# yBrainA1-11March2015.net
KiCad netlist of a schematic drawn in EAGLE
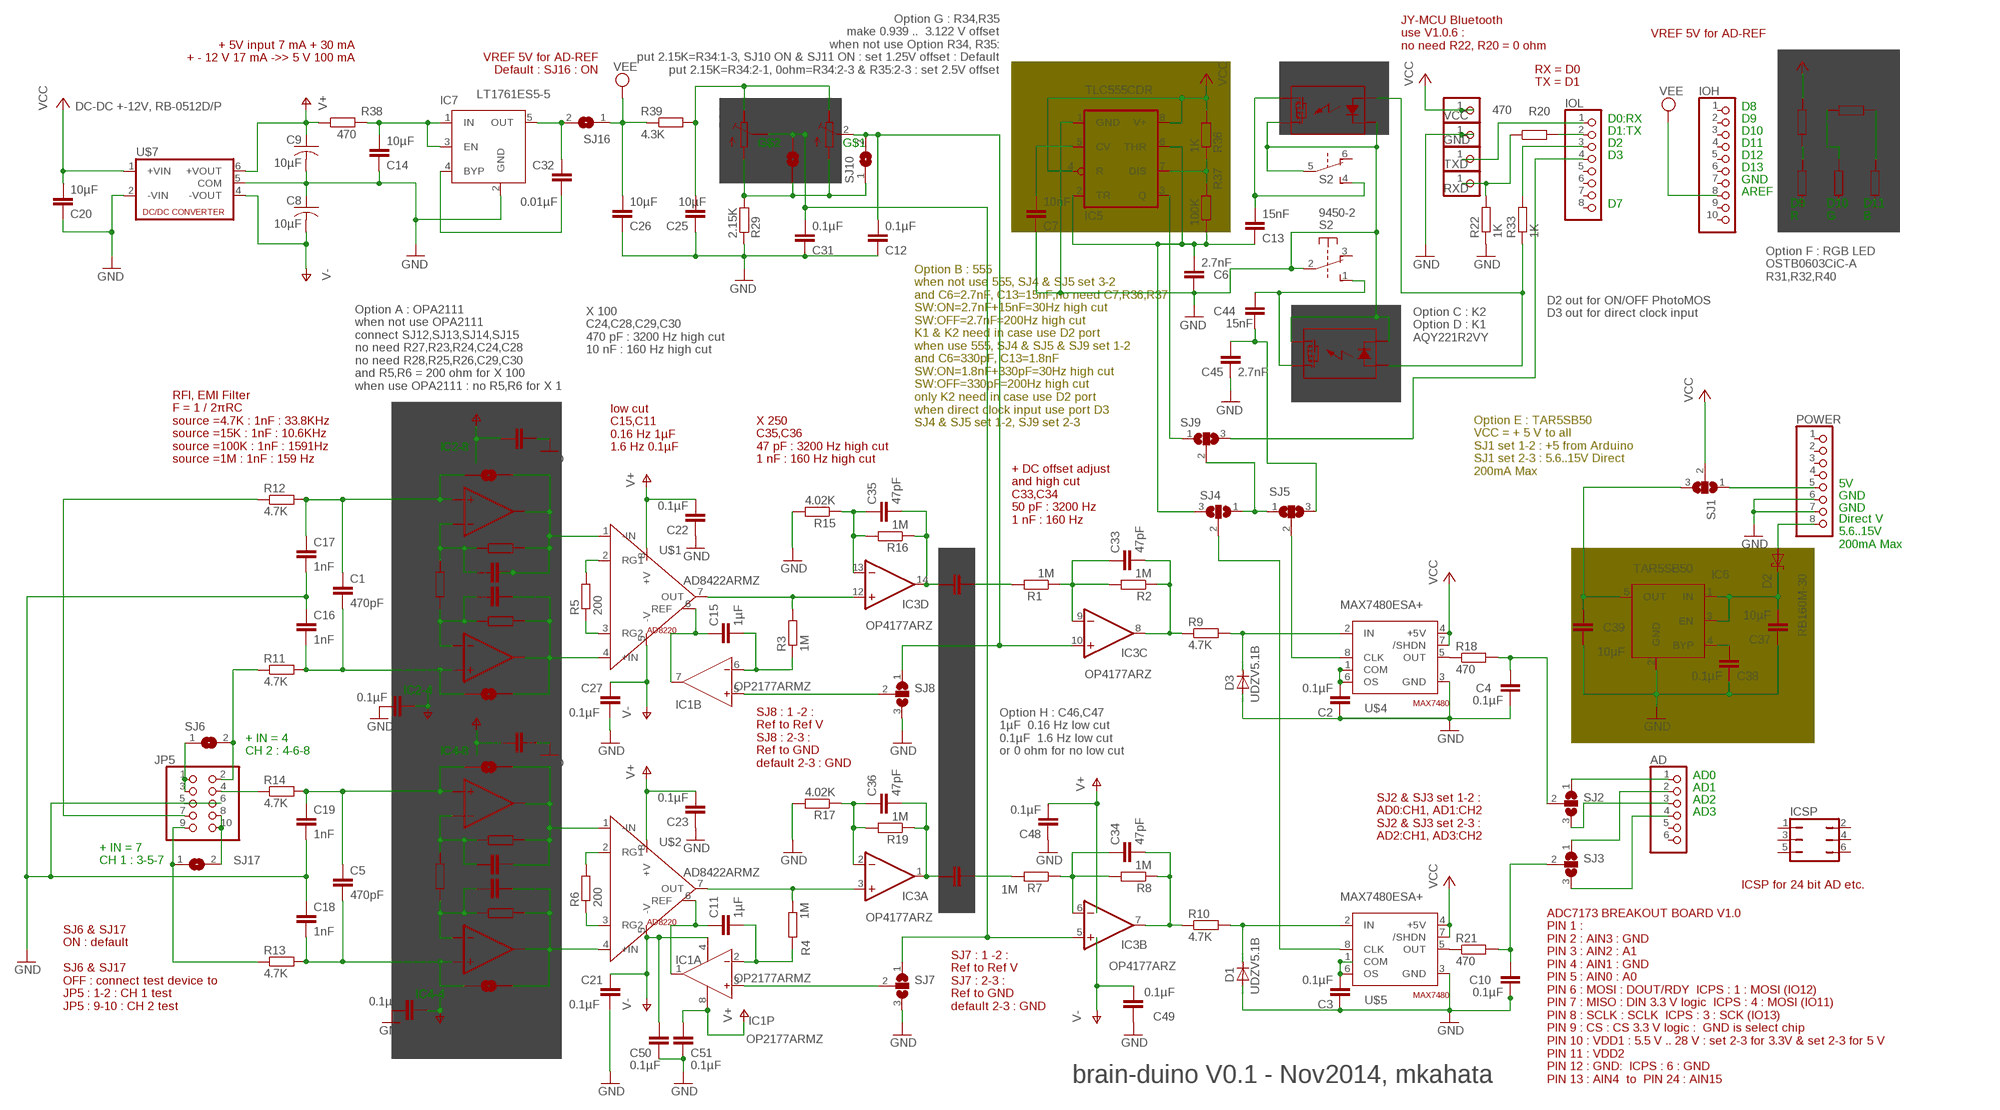
[diagram p0: schematic, sheet 1]

(export (version "E")
  (design (tool "Eeschema 10.0.6"))
  (components
    (comp (ref "AD")
      (value "PINHD-1X6")
      (footprint "eagle-import:1X06")
      (libsource (lib "eagle-import") (part "PINHD-1X6"))
    )
    (comp (ref "C1")
      (value "470pF")
      (footprint "eagle-import:C0805")
      (libsource (lib "eagle-import") (part "C-EUC0805"))
    )
    (comp (ref "C2")
      (value "0.1µF")
      (footprint "eagle-import:C0805")
      (libsource (lib "eagle-import") (part "C-EUC0805"))
    )
    (comp (ref "C3")
      (value "0.1µF")
      (footprint "eagle-import:C0805")
      (libsource (lib "eagle-import") (part "C-EUC0805"))
    )
    (comp (ref "C4")
      (value "0.1µF")
      (footprint "eagle-import:C0805")
      (libsource (lib "eagle-import") (part "C-EUC0805"))
    )
    (comp (ref "C5")
      (value "470pF")
      (footprint "eagle-import:C0805")
      (libsource (lib "eagle-import") (part "C-EUC0805"))
    )
    (comp (ref "C6")
      (value "2.7nF")
      (footprint "eagle-import:C0805")
      (libsource (lib "eagle-import") (part "C-EUC0805"))
    )
    (comp (ref "C7")
      (value "10nF")
      (footprint "eagle-import:C0805")
      (libsource (lib "eagle-import") (part "C-EUC0805"))
    )
    (comp (ref "C8")
      (value "10µF")
      (footprint "eagle-import:C0805")
      (libsource (lib "eagle-import") (part "C-USC0805"))
    )
    (comp (ref "C9")
      (value "10µF")
      (footprint "eagle-import:C0805")
      (libsource (lib "eagle-import") (part "C-USC0805"))
    )
    (comp (ref "C10")
      (value "0.1µF")
      (footprint "eagle-import:C0805")
      (libsource (lib "eagle-import") (part "C-EUC0805"))
    )
    (comp (ref "C11")
      (value "1µF")
      (footprint "eagle-import:C0805")
      (libsource (lib "eagle-import") (part "C-EUC0805"))
    )
    (comp (ref "C12")
      (value "0.1µF")
      (footprint "eagle-import:C0805")
      (libsource (lib "eagle-import") (part "C-EUC0805"))
    )
    (comp (ref "C13")
      (value "15nF")
      (footprint "eagle-import:C0805")
      (libsource (lib "eagle-import") (part "C-EUC0805"))
    )
    (comp (ref "C14")
      (value "10µF")
      (footprint "eagle-import:C0805")
      (libsource (lib "eagle-import") (part "C-EUC0805"))
    )
    (comp (ref "C15")
      (value "1µF")
      (footprint "eagle-import:C0805")
      (libsource (lib "eagle-import") (part "C-EUC0805"))
    )
    (comp (ref "C16")
      (value "1nF")
      (footprint "eagle-import:C0805")
      (libsource (lib "eagle-import") (part "C-EUC0805"))
    )
    (comp (ref "C17")
      (value "1nF")
      (footprint "eagle-import:C0805")
      (libsource (lib "eagle-import") (part "C-EUC0805"))
    )
    (comp (ref "C18")
      (value "1nF")
      (footprint "eagle-import:C0805")
      (libsource (lib "eagle-import") (part "C-EUC0805"))
    )
    (comp (ref "C19")
      (value "1nF")
      (footprint "eagle-import:C0805")
      (libsource (lib "eagle-import") (part "C-EUC0805"))
    )
    (comp (ref "C20")
      (value "10µF")
      (footprint "eagle-import:C0805")
      (libsource (lib "eagle-import") (part "C-EUC0805"))
    )
    (comp (ref "C21")
      (value "0.1µF")
      (footprint "eagle-import:C0805")
      (libsource (lib "eagle-import") (part "C-EUC0805"))
    )
    (comp (ref "C22")
      (value "0.1µF")
      (footprint "eagle-import:C0805")
      (libsource (lib "eagle-import") (part "C-EUC0805"))
    )
    (comp (ref "C23")
      (value "0.1µF")
      (footprint "eagle-import:C0805")
      (libsource (lib "eagle-import") (part "C-EUC0805"))
    )
    (comp (ref "C24")
      (value "470pF")
      (footprint "eagle-import:C0805")
      (libsource (lib "eagle-import") (part "C-EUC0805"))
    )
    (comp (ref "C25")
      (value "10µF")
      (footprint "eagle-import:C0805")
      (libsource (lib "eagle-import") (part "C-EUC0805"))
    )
    (comp (ref "C26")
      (value "10µF")
      (footprint "eagle-import:C0805")
      (libsource (lib "eagle-import") (part "C-EUC0805"))
    )
    (comp (ref "C27")
      (value "0.1µF")
      (footprint "eagle-import:C0805")
      (libsource (lib "eagle-import") (part "C-EUC0805"))
    )
    (comp (ref "C28")
      (value "470pF")
      (footprint "eagle-import:C0805")
      (libsource (lib "eagle-import") (part "C-EUC0805"))
    )
    (comp (ref "C29")
      (value "470pF")
      (footprint "eagle-import:C0805")
      (libsource (lib "eagle-import") (part "C-EUC0805"))
    )
    (comp (ref "C30")
      (value "470pF")
      (footprint "eagle-import:C0805")
      (libsource (lib "eagle-import") (part "C-EUC0805"))
    )
    (comp (ref "C31")
      (value "0.1µF")
      (footprint "eagle-import:C0805")
      (libsource (lib "eagle-import") (part "C-EUC0805"))
    )
    (comp (ref "C32")
      (value "0.01µF")
      (footprint "eagle-import:C0805")
      (libsource (lib "eagle-import") (part "C-EUC0805"))
    )
    (comp (ref "C33")
      (value "47pF")
      (footprint "eagle-import:C0805")
      (libsource (lib "eagle-import") (part "C-EUC0805"))
    )
    (comp (ref "C34")
      (value "47pF")
      (footprint "eagle-import:C0805")
      (libsource (lib "eagle-import") (part "C-EUC0805"))
    )
    (comp (ref "C35")
      (value "47pF")
      (footprint "eagle-import:C0805")
      (libsource (lib "eagle-import") (part "C-EUC0805"))
    )
    (comp (ref "C36")
      (value "47pF")
      (footprint "eagle-import:C0805")
      (libsource (lib "eagle-import") (part "C-EUC0805"))
    )
    (comp (ref "C37")
      (value "10µF")
      (footprint "eagle-import:C0805")
      (libsource (lib "eagle-import") (part "C-EUC0805"))
    )
    (comp (ref "C38")
      (value "0.1µF")
      (footprint "eagle-import:C0805")
      (libsource (lib "eagle-import") (part "C-EUC0805"))
    )
    (comp (ref "C39")
      (value "10µF")
      (footprint "eagle-import:C0805")
      (libsource (lib "eagle-import") (part "C-EUC0805"))
    )
    (comp (ref "C40")
      (value "0.1µF")
      (footprint "eagle-import:C0805")
      (libsource (lib "eagle-import") (part "C-EUC0805"))
    )
    (comp (ref "C41")
      (value "0.1µF")
      (footprint "eagle-import:C0805")
      (libsource (lib "eagle-import") (part "C-EUC0805"))
    )
    (comp (ref "C42")
      (value "0.1µF")
      (footprint "eagle-import:C0805")
      (libsource (lib "eagle-import") (part "C-EUC0805"))
    )
    (comp (ref "C43")
      (value "0.1µF")
      (footprint "eagle-import:C0805")
      (libsource (lib "eagle-import") (part "C-EUC0805"))
    )
    (comp (ref "C44")
      (value "15nF")
      (footprint "eagle-import:C0805")
      (libsource (lib "eagle-import") (part "C-EUC0805"))
    )
    (comp (ref "C45")
      (value "2.7nF")
      (footprint "eagle-import:C0805")
      (libsource (lib "eagle-import") (part "C-EUC0805"))
    )
    (comp (ref "C46")
      (value "1µF")
      (footprint "eagle-import:C0805")
      (libsource (lib "eagle-import") (part "C-EUC0805"))
    )
    (comp (ref "C47")
      (value "1µF")
      (footprint "eagle-import:C0805")
      (libsource (lib "eagle-import") (part "C-EUC0805"))
    )
    (comp (ref "C48")
      (value "0.1µF")
      (footprint "eagle-import:C0805")
      (libsource (lib "eagle-import") (part "C-EUC0805"))
    )
    (comp (ref "C49")
      (value "0.1µF")
      (footprint "eagle-import:C0805")
      (libsource (lib "eagle-import") (part "C-EUC0805"))
    )
    (comp (ref "C50")
      (value "0.1µF")
      (footprint "eagle-import:C0805")
      (libsource (lib "eagle-import") (part "C-EUC0805"))
    )
    (comp (ref "C51")
      (value "0.1µF")
      (footprint "eagle-import:C0805")
      (libsource (lib "eagle-import") (part "C-EUC0805"))
    )
    (comp (ref "D1")
      (value "UDZV5.1B")
      (footprint "eagle-import:SOD110-R")
      (libsource (lib "eagle-import") (part "DIODE-SOD110-R"))
    )
    (comp (ref "D2")
      (value "RB160M-30")
      (footprint "eagle-import:POWERDI323")
      (libsource (lib "eagle-import") (part "PD3S160"))
    )
    (comp (ref "D3")
      (value "UDZV5.1B")
      (footprint "eagle-import:SOD110-R")
      (libsource (lib "eagle-import") (part "DIODE-SOD110-R"))
    )
    (comp (ref "GND")
      (value "PINHD-1X1")
      (footprint "eagle-import:1X01")
      (libsource (lib "eagle-import") (part "PINHD-1X1"))
    )
    (comp (ref "IC1")
      (value "OP2177ARMZ")
      (footprint "eagle-import:MSOP08")
      (fields (field (name "MPN") "AD8656ARMZ"))
      (libsource (lib "eagle-import") (part "AD8656RM"))
    )
    (comp (ref "IC2")
      (value "OPA2111KP")
      (footprint "eagle-import:DIL08")
      (libsource (lib "eagle-import") (part "OPA2111P"))
    )
    (comp (ref "IC3")
      (value "OP4177ARZ")
      (footprint "eagle-import:SO14")
      (libsource (lib "eagle-import") (part "TL064D"))
    )
    (comp (ref "IC4")
      (value "OPA2111KP")
      (footprint "eagle-import:DIL08")
      (libsource (lib "eagle-import") (part "OPA2111P"))
    )
    (comp (ref "IC5")
      (value "TLC555CDR")
      (footprint "eagle-import:SO08")
      (libsource (lib "eagle-import") (part "555DLM"))
    )
    (comp (ref "IC6")
      (value "TAR5SB50")
      (footprint "eagle-import:SOT23-5")
      (libsource (lib "eagle-import") (part "MIC5219XX"))
    )
    (comp (ref "IC7")
      (value "LT1761ES5-5")
      (footprint "eagle-import:SOT23-5")
      (libsource (lib "eagle-import") (part "MIC5219XX"))
    )
    (comp (ref "ICSP")
      (value "JP3Q")
      (footprint "eagle-import:JP3Q")
      (libsource (lib "eagle-import") (part "JP3Q"))
    )
    (comp (ref "IOH")
      (value "PINHD-1X10")
      (footprint "eagle-import:1X10")
      (libsource (lib "eagle-import") (part "PINHD-1X10"))
    )
    (comp (ref "IOL")
      (value "PINHD-1X8")
      (footprint "eagle-import:1X08")
      (libsource (lib "eagle-import") (part "PINHD-1X8"))
    )
    (comp (ref "JP5")
      (value "PINHD-2X5/90")
      (footprint "eagle-import:2X05_90")
      (libsource (lib "eagle-import") (part "PINHD-2X5/90"))
    )
    (comp (ref "K1")
      (value "AQY221R2VY")
      (footprint "eagle-import:SSOP4")
      (fields (field (name "MF") "AROMAT/ MATSUSHITA") (field (name "MPN") "AQY221R2V"))
      (libsource (lib "eagle-import") (part "AQY2212VR"))
    )
    (comp (ref "K2")
      (value "AQY221R2VY")
      (footprint "eagle-import:SSOP4")
      (fields (field (name "MF") "AROMAT/ MATSUSHITA") (field (name "MPN") "AQY221R2V"))
      (libsource (lib "eagle-import") (part "AQY2212VR"))
    )
    (comp (ref "POWER")
      (value "PINHD-1X8")
      (footprint "eagle-import:1X08")
      (libsource (lib "eagle-import") (part "PINHD-1X8"))
    )
    (comp (ref "R1")
      (value "1M")
      (footprint "eagle-import:R0805")
      (libsource (lib "eagle-import") (part "R-EU_R0805"))
    )
    (comp (ref "R2")
      (value "1M")
      (footprint "eagle-import:R0805")
      (libsource (lib "eagle-import") (part "R-EU_R0805"))
    )
    (comp (ref "R3")
      (value "1M")
      (footprint "eagle-import:R0805")
      (libsource (lib "eagle-import") (part "R-EU_R0805"))
    )
    (comp (ref "R4")
      (value "1M")
      (footprint "eagle-import:R0805")
      (libsource (lib "eagle-import") (part "R-EU_R0805"))
    )
    (comp (ref "R5")
      (value "200")
      (footprint "eagle-import:R0805")
      (libsource (lib "eagle-import") (part "R-EU_R0805"))
    )
    (comp (ref "R6")
      (value "200")
      (footprint "eagle-import:R0805")
      (libsource (lib "eagle-import") (part "R-EU_R0805"))
    )
    (comp (ref "R7")
      (value "1M")
      (footprint "eagle-import:R0805")
      (libsource (lib "eagle-import") (part "R-EU_R0805"))
    )
    (comp (ref "R8")
      (value "1M")
      (footprint "eagle-import:R0805")
      (libsource (lib "eagle-import") (part "R-EU_R0805"))
    )
    (comp (ref "R9")
      (value "4.7K")
      (footprint "eagle-import:R0805")
      (libsource (lib "eagle-import") (part "R-EU_R0805"))
    )
    (comp (ref "R10")
      (value "4.7K")
      (footprint "eagle-import:R0805")
      (libsource (lib "eagle-import") (part "R-EU_R0805"))
    )
    (comp (ref "R11")
      (value "4.7K")
      (footprint "eagle-import:R0805")
      (libsource (lib "eagle-import") (part "R-EU_R0805"))
    )
    (comp (ref "R12")
      (value "4.7K")
      (footprint "eagle-import:R0805")
      (libsource (lib "eagle-import") (part "R-EU_R0805"))
    )
    (comp (ref "R13")
      (value "4.7K")
      (footprint "eagle-import:R0805")
      (libsource (lib "eagle-import") (part "R-EU_R0805"))
    )
    (comp (ref "R14")
      (value "4.7K")
      (footprint "eagle-import:R0805")
      (libsource (lib "eagle-import") (part "R-EU_R0805"))
    )
    (comp (ref "R15")
      (value "4.02K")
      (footprint "eagle-import:R0805")
      (libsource (lib "eagle-import") (part "R-EU_R0805"))
    )
    (comp (ref "R16")
      (value "1M")
      (footprint "eagle-import:R0805")
      (libsource (lib "eagle-import") (part "R-EU_R0805"))
    )
    (comp (ref "R17")
      (value "4.02K")
      (footprint "eagle-import:R0805")
      (libsource (lib "eagle-import") (part "R-EU_R0805"))
    )
    (comp (ref "R18")
      (value "470")
      (footprint "eagle-import:R0805")
      (libsource (lib "eagle-import") (part "R-EU_R0805"))
    )
    (comp (ref "R19")
      (value "1M")
      (footprint "eagle-import:R0805")
      (libsource (lib "eagle-import") (part "R-EU_R0805"))
    )
    (comp (ref "R20")
      (value "470")
      (footprint "eagle-import:R0805")
      (libsource (lib "eagle-import") (part "R-EU_R0805"))
    )
    (comp (ref "R21")
      (value "470")
      (footprint "eagle-import:R0805")
      (libsource (lib "eagle-import") (part "R-EU_R0805"))
    )
    (comp (ref "R22")
      (value "1K")
      (footprint "eagle-import:R0805")
      (libsource (lib "eagle-import") (part "R-EU_R0805"))
    )
    (comp (ref "R23")
      (value "100K")
      (footprint "eagle-import:R0805")
      (libsource (lib "eagle-import") (part "R-EU_R0805"))
    )
    (comp (ref "R24")
      (value "100K")
      (footprint "eagle-import:R0805")
      (libsource (lib "eagle-import") (part "R-EU_R0805"))
    )
    (comp (ref "R25")
      (value "100K")
      (footprint "eagle-import:R0805")
      (libsource (lib "eagle-import") (part "R-EU_R0805"))
    )
    (comp (ref "R26")
      (value "100K")
      (footprint "eagle-import:R0805")
      (libsource (lib "eagle-import") (part "R-EU_R0805"))
    )
    (comp (ref "R27")
      (value "2K")
      (footprint "eagle-import:R0805")
      (libsource (lib "eagle-import") (part "R-EU_R0805"))
    )
    (comp (ref "R28")
      (value "2K")
      (footprint "eagle-import:R0805")
      (libsource (lib "eagle-import") (part "R-EU_R0805"))
    )
    (comp (ref "R29")
      (value "2.15K")
      (footprint "eagle-import:R0805")
      (libsource (lib "eagle-import") (part "R-EU_R0805"))
    )
    (comp (ref "R30")
      (value "LED")
      (footprint "eagle-import:R0402")
      (libsource (lib "eagle-import") (part "R-EU_R0402"))
    )
    (comp (ref "R31")
      (value "1K")
      (footprint "eagle-import:R0402")
      (libsource (lib "eagle-import") (part "R-EU_R0402"))
    )
    (comp (ref "R32")
      (value "1K")
      (footprint "eagle-import:R0402")
      (libsource (lib "eagle-import") (part "R-EU_R0402"))
    )
    (comp (ref "R33")
      (value "1K")
      (footprint "eagle-import:R0805")
      (libsource (lib "eagle-import") (part "R-EU_R0805"))
    )
    (comp (ref "R34")
      (value "10K")
      (footprint "eagle-import:RTRIM5X")
      (libsource (lib "eagle-import") (part "R-TRIMM5X"))
    )
    (comp (ref "R35")
      (value "10K")
      (footprint "eagle-import:RTRIM5X")
      (libsource (lib "eagle-import") (part "R-TRIMM5X"))
    )
    (comp (ref "R36")
      (value "1K")
      (footprint "eagle-import:R0805")
      (libsource (lib "eagle-import") (part "R-EU_R0805"))
    )
    (comp (ref "R37")
      (value "100K")
      (footprint "eagle-import:R0805")
      (libsource (lib "eagle-import") (part "R-EU_R0805"))
    )
    (comp (ref "R38")
      (value "470")
      (footprint "eagle-import:R0805")
      (libsource (lib "eagle-import") (part "R-EU_R0805"))
    )
    (comp (ref "R39")
      (value "4.3K")
      (footprint "eagle-import:R0805")
      (libsource (lib "eagle-import") (part "R-EU_R0805"))
    )
    (comp (ref "R40")
      (value "1K")
      (footprint "eagle-import:R0402")
      (libsource (lib "eagle-import") (part "R-EU_R0402"))
    )
    (comp (ref "R41")
      (value "LED")
      (footprint "eagle-import:R0402")
      (libsource (lib "eagle-import") (part "R-EU_R0402"))
    )
    (comp (ref "RXD")
      (value "PINHD-1X1")
      (footprint "eagle-import:1X01")
      (libsource (lib "eagle-import") (part "PINHD-1X1"))
    )
    (comp (ref "S2")
      (value "9450-2")
      (footprint "eagle-import:9450-2")
      (libsource (lib "eagle-import") (part "9450-2"))
    )
    (comp (ref "SJ1")
      (value "SJ2W")
      (footprint "eagle-import:SJ_2")
      (libsource (lib "eagle-import") (part "SJ2W"))
    )
    (comp (ref "SJ2")
      (value "SJ2W")
      (footprint "eagle-import:SJ_2")
      (libsource (lib "eagle-import") (part "SJ2W"))
    )
    (comp (ref "SJ3")
      (value "SJ2W")
      (footprint "eagle-import:SJ_2")
      (libsource (lib "eagle-import") (part "SJ2W"))
    )
    (comp (ref "SJ4")
      (value "SJ2W")
      (footprint "eagle-import:SJ_2")
      (libsource (lib "eagle-import") (part "SJ2W"))
    )
    (comp (ref "SJ5")
      (value "SJ2W")
      (footprint "eagle-import:SJ_2")
      (libsource (lib "eagle-import") (part "SJ2W"))
    )
    (comp (ref "SJ6") (value "SJ") (footprint "eagle-import:SJ") (libsource (lib "eagle-import") (part "SJ")))
    (comp (ref "SJ7")
      (value "SJ2W")
      (footprint "eagle-import:SJ_2")
      (libsource (lib "eagle-import") (part "SJ2W"))
    )
    (comp (ref "SJ8")
      (value "SJ2W")
      (footprint "eagle-import:SJ_2")
      (libsource (lib "eagle-import") (part "SJ2W"))
    )
    (comp (ref "SJ9")
      (value "SJ2W")
      (footprint "eagle-import:SJ_2")
      (libsource (lib "eagle-import") (part "SJ2W"))
    )
    (comp (ref "SJ10")
      (value "SJ")
      (footprint "eagle-import:SJ")
      (libsource (lib "eagle-import") (part "SJ"))
    )
    (comp (ref "SJ11")
      (value "SJ")
      (footprint "eagle-import:SJ")
      (libsource (lib "eagle-import") (part "SJ"))
    )
    (comp (ref "SJ12")
      (value "SJ")
      (footprint "eagle-import:SJ")
      (libsource (lib "eagle-import") (part "SJ"))
    )
    (comp (ref "SJ13")
      (value "SJ")
      (footprint "eagle-import:SJ")
      (libsource (lib "eagle-import") (part "SJ"))
    )
    (comp (ref "SJ14")
      (value "SJ")
      (footprint "eagle-import:SJ")
      (libsource (lib "eagle-import") (part "SJ"))
    )
    (comp (ref "SJ15")
      (value "SJ")
      (footprint "eagle-import:SJ")
      (libsource (lib "eagle-import") (part "SJ"))
    )
    (comp (ref "SJ16")
      (value "SJ")
      (footprint "eagle-import:SJ")
      (libsource (lib "eagle-import") (part "SJ"))
    )
    (comp (ref "SJ17")
      (value "SJ")
      (footprint "eagle-import:SJ")
      (libsource (lib "eagle-import") (part "SJ"))
    )
    (comp (ref "TXD")
      (value "PINHD-1X1")
      (footprint "eagle-import:1X01")
      (libsource (lib "eagle-import") (part "PINHD-1X1"))
    )
    (comp (ref "U$1")
      (value "AD8422ARMZ")
      (footprint "eagle-import:AD8220")
      (libsource (lib "eagle-import") (part "AD8220"))
    )
    (comp (ref "U$2")
      (value "AD8422ARMZ")
      (footprint "eagle-import:AD8220")
      (libsource (lib "eagle-import") (part "AD8220"))
    )
    (comp (ref "U$4")
      (value "MAX7480ESA+")
      (footprint "eagle-import:MAX7480")
      (libsource (lib "eagle-import") (part "MAX7480"))
    )
    (comp (ref "U$5")
      (value "MAX7480ESA+")
      (footprint "eagle-import:MAX7480")
      (libsource (lib "eagle-import") (part "MAX7480"))
    )
    (comp (ref "U$7")
      (value "DC-DC +-12V, RB-0512D/P")
      (footprint "eagle-import:RB-0515D")
      (libsource (lib "eagle-import") (part "RB-0515D"))
    )
    (comp (ref "VCC")
      (value "PINHD-1X1")
      (footprint "eagle-import:1X01")
      (libsource (lib "eagle-import") (part "PINHD-1X1"))
    )
  )
  (nets
    (net (code "1") (name "GND") (class "Default")
      (node (ref "C10") (pin "1") (pinfunction "1_1") (pintype "passive"))
      (node (ref "C12") (pin "1") (pinfunction "1_1") (pintype "passive"))
      (node (ref "C14") (pin "1") (pinfunction "1_1") (pintype "passive"))
      (node (ref "C16") (pin "1") (pinfunction "1_1") (pintype "passive"))
      (node (ref "C17") (pin "2") (pinfunction "2_2") (pintype "passive"))
      (node (ref "C18") (pin "1") (pinfunction "1_1") (pintype "passive"))
      (node (ref "C19") (pin "2") (pinfunction "2_2") (pintype "passive"))
      (node (ref "C2") (pin "1") (pinfunction "1_1") (pintype "passive"))
      (node (ref "C20") (pin "1") (pinfunction "1_1") (pintype "passive"))
      (node (ref "C21") (pin "2") (pinfunction "2_2") (pintype "passive"))
      (node (ref "C22") (pin "1") (pinfunction "1_1") (pintype "passive"))
      (node (ref "C23") (pin "1") (pinfunction "1_1") (pintype "passive"))
      (node (ref "C25") (pin "1") (pinfunction "1_1") (pintype "passive"))
      (node (ref "C26") (pin "1") (pinfunction "1_1") (pintype "passive"))
      (node (ref "C27") (pin "2") (pinfunction "2_2") (pintype "passive"))
      (node (ref "C3") (pin "1") (pinfunction "1_1") (pintype "passive"))
      (node (ref "C31") (pin "1") (pinfunction "1_1") (pintype "passive"))
      (node (ref "C37") (pin "1") (pinfunction "1_1") (pintype "passive"))
      (node (ref "C38") (pin "1") (pinfunction "1_1") (pintype "passive"))
      (node (ref "C39") (pin "1") (pinfunction "1_1") (pintype "passive"))
      (node (ref "C4") (pin "1") (pinfunction "1_1") (pintype "passive"))
      (node (ref "C40") (pin "1") (pinfunction "1_1") (pintype "passive"))
      (node (ref "C41") (pin "2") (pinfunction "2_2") (pintype "passive"))
      (node (ref "C42") (pin "2") (pinfunction "2_2") (pintype "passive"))
      (node (ref "C43") (pin "2") (pinfunction "2_2") (pintype "passive"))
      (node (ref "C45") (pin "1") (pinfunction "1_1") (pintype "passive"))
      (node (ref "C48") (pin "1") (pinfunction "1_1") (pintype "passive"))
      (node (ref "C49") (pin "1") (pinfunction "1_1") (pintype "passive"))
      (node (ref "C50") (pin "2") (pinfunction "2_2") (pintype "passive"))
      (node (ref "C51") (pin "2") (pinfunction "2_2") (pintype "passive"))
      (node (ref "C6") (pin "1") (pinfunction "1_1") (pintype "passive"))
      (node (ref "C7") (pin "1") (pinfunction "1_1") (pintype "passive"))
      (node (ref "C8") (pin "1") (pinfunction "1_1") (pintype "passive"))
      (node (ref "C9") (pin "2") (pinfunction "2_2") (pintype "passive"))
      (node (ref "D1") (pin "A") (pinfunction "A_A") (pintype "passive"))
      (node (ref "D3") (pin "A") (pinfunction "A_A") (pintype "passive"))
      (node (ref "GND") (pin "1") (pinfunction "1_1") (pintype "passive"))
      (node (ref "IC5") (pin "1") (pinfunction "GND_1") (pintype "power_in"))
      (node (ref "IC6") (pin "2") (pinfunction "GND_2") (pintype "power_in"))
      (node (ref "IC7") (pin "2") (pinfunction "GND_2") (pintype "power_in"))
      (node (ref "JP5") (pin "5") (pinfunction "5_5") (pintype "passive"))
      (node (ref "JP5") (pin "6") (pinfunction "6_6") (pintype "passive"))
      (node (ref "K1") (pin "2") (pinfunction "K_2") (pintype "passive"))
      (node (ref "K1") (pin "3") (pinfunction "DS2_3") (pintype "passive"))
      (node (ref "K2") (pin "2") (pinfunction "K_2") (pintype "passive"))
      (node (ref "K2") (pin "3") (pinfunction "DS2_3") (pintype "passive"))
      (node (ref "POWER") (pin "6") (pinfunction "6_6") (pintype "passive"))
      (node (ref "POWER") (pin "7") (pinfunction "7_7") (pintype "passive"))
      (node (ref "R15") (pin "2") (pinfunction "2_2") (pintype "passive"))
      (node (ref "R17") (pin "2") (pinfunction "2_2") (pintype "passive"))
      (node (ref "R22") (pin "1") (pinfunction "1_1") (pintype "passive"))
      (node (ref "R29") (pin "1") (pinfunction "1_1") (pintype "passive"))
      (node (ref "S2") (pin "2") (pinfunction "P_2") (pintype "passive"))
      (node (ref "S2") (pin "5") (pinfunction "P_5") (pintype "passive"))
      (node (ref "SJ7") (pin "3") (pinfunction "3_3") (pintype "passive"))
      (node (ref "SJ8") (pin "3") (pinfunction "3_3") (pintype "passive"))
      (node (ref "U$4") (pin "3") (pinfunction "GND_3") (pintype "power_in"))
      (node (ref "U$5") (pin "3") (pinfunction "GND_3") (pintype "power_in"))
      (node (ref "U$7") (pin "2") (pinfunction "-VIN_2") (pintype "passive"))
      (node (ref "U$7") (pin "5") (pinfunction "COM_5") (pintype "passive"))
    )
    (net (code "2") (name "Net-(AD-Pad1)") (class "Default")
      (node (ref "AD") (pin "1") (pinfunction "1_1") (pintype "passive"))
      (node (ref "SJ2") (pin "1") (pinfunction "1_1") (pintype "passive"))
    )
    (net (code "3") (name "Net-(AD-Pad2)") (class "Default")
      (node (ref "AD") (pin "2") (pinfunction "2_2") (pintype "passive"))
      (node (ref "SJ3") (pin "1") (pinfunction "1_1") (pintype "passive"))
    )
    (net (code "4") (name "Net-(AD-Pad3)") (class "Default")
      (node (ref "AD") (pin "3") (pinfunction "3_3") (pintype "passive"))
      (node (ref "SJ2") (pin "3") (pinfunction "3_3") (pintype "passive"))
    )
    (net (code "5") (name "Net-(AD-Pad4)") (class "Default")
      (node (ref "AD") (pin "4") (pinfunction "4_4") (pintype "passive"))
      (node (ref "SJ3") (pin "3") (pinfunction "3_3") (pintype "passive"))
    )
    (net (code "6") (name "Net-(C4-Pad2)") (class "Default")
      (node (ref "C4") (pin "2") (pinfunction "2_2") (pintype "passive"))
      (node (ref "R18") (pin "2") (pinfunction "2_2") (pintype "passive"))
      (node (ref "SJ2") (pin "2") (pinfunction "2_2") (pintype "passive"))
    )
    (net (code "7") (name "Net-(C10-Pad2)") (class "Default")
      (node (ref "C10") (pin "2") (pinfunction "2_2") (pintype "passive"))
      (node (ref "R21") (pin "2") (pinfunction "2_2") (pintype "passive"))
      (node (ref "SJ3") (pin "2") (pinfunction "2_2") (pintype "passive"))
    )
    (net (code "8") (name "Net-(C44-Pad1)") (class "Default")
      (node (ref "C44") (pin "1") (pinfunction "1_1") (pintype "passive"))
      (node (ref "C45") (pin "2") (pinfunction "2_2") (pintype "passive"))
      (node (ref "SJ5") (pin "3") (pinfunction "3_3") (pintype "passive"))
    )
    (net (code "9") (name "Net-(C46-Pad2)") (class "Default")
      (node (ref "C46") (pin "2") (pinfunction "2_2") (pintype "passive"))
      (node (ref "R1") (pin "2") (pinfunction "2_2") (pintype "passive"))
    )
    (net (code "10") (name "Net-(C47-Pad2)") (class "Default")
      (node (ref "C47") (pin "2") (pinfunction "2_2") (pintype "passive"))
      (node (ref "R7") (pin "2") (pinfunction "2_2") (pintype "passive"))
    )
    (net (code "11") (name "Net-(D2-PadA)") (class "Default")
      (node (ref "D2") (pin "A") (pinfunction "A_A") (pintype "passive"))
      (node (ref "POWER") (pin "8") (pinfunction "8_8") (pintype "passive"))
    )
    (net (code "12") (name "Net-(IC1A-IN+)") (class "Default")
      (node (ref "IC1") (pin "3") (pinfunction "IN+_3") (pintype "input"))
      (node (ref "SJ7") (pin "2") (pinfunction "2_2") (pintype "passive"))
    )
    (net (code "13") (name "Net-(IC1A-IN-)") (class "Default")
      (node (ref "C11") (pin "2") (pinfunction "2_2") (pintype "passive"))
      (node (ref "IC1") (pin "2") (pinfunction "IN-_2") (pintype "input"))
      (node (ref "R4") (pin "1") (pinfunction "1_1") (pintype "passive"))
    )
    (net (code "14") (name "Net-(IC1A-OUT)") (class "Default")
      (node (ref "C11") (pin "1") (pinfunction "1_1") (pintype "passive"))
      (node (ref "IC1") (pin "1") (pinfunction "OUT_1") (pintype "output"))
      (node (ref "U$2") (pin "6") (pinfunction "REF_6") (pintype "input"))
    )
    (net (code "15") (name "Net-(IC1B-IN+)") (class "Default")
      (node (ref "IC1") (pin "5") (pinfunction "IN+_5") (pintype "input"))
      (node (ref "SJ8") (pin "2") (pinfunction "2_2") (pintype "passive"))
    )
    (net (code "16") (name "Net-(IC1B-IN-)") (class "Default")
      (node (ref "C15") (pin "2") (pinfunction "2_2") (pintype "passive"))
      (node (ref "IC1") (pin "6") (pinfunction "IN-_6") (pintype "input"))
      (node (ref "R3") (pin "1") (pinfunction "1_1") (pintype "passive"))
    )
    (net (code "17") (name "Net-(IC1B-OUT)") (class "Default")
      (node (ref "C15") (pin "1") (pinfunction "1_1") (pintype "passive"))
      (node (ref "IC1") (pin "7") (pinfunction "OUT_7") (pintype "output"))
      (node (ref "U$1") (pin "6") (pinfunction "REF_6") (pintype "input"))
    )
    (net (code "18") (name "Net-(IC2A-+IN)") (class "Default")
      (node (ref "C1") (pin "1") (pinfunction "1_1") (pintype "passive"))
      (node (ref "C17") (pin "1") (pinfunction "1_1") (pintype "passive"))
      (node (ref "IC2") (pin "3") (pinfunction "+IN_3") (pintype "input"))
      (node (ref "R12") (pin "2") (pinfunction "2_2") (pintype "passive"))
      (node (ref "SJ12") (pin "2") (pinfunction "2_2") (pintype "passive"))
    )
    (net (code "19") (name "Net-(IC2A--IN)") (class "Default")
      (node (ref "C24") (pin "1") (pinfunction "1_1") (pintype "passive"))
      (node (ref "IC2") (pin "2") (pinfunction "-IN_2") (pintype "input"))
      (node (ref "R23") (pin "1") (pinfunction "1_1") (pintype "passive"))
      (node (ref "R27") (pin "2") (pinfunction "2_2") (pintype "passive"))
    )
    (net (code "20") (name "Net-(IC2A-OUT)") (class "Default")
      (node (ref "C24") (pin "2") (pinfunction "2_2") (pintype "passive"))
      (node (ref "IC2") (pin "1") (pinfunction "OUT_1") (pintype "output"))
      (node (ref "R23") (pin "2") (pinfunction "2_2") (pintype "passive"))
      (node (ref "SJ12") (pin "1") (pinfunction "1_1") (pintype "passive"))
      (node (ref "U$1") (pin "1") (pinfunction "-IN_1") (pintype "input"))
    )
    (net (code "21") (name "Net-(IC2B-+IN)") (class "Default")
      (node (ref "C1") (pin "2") (pinfunction "2_2") (pintype "passive"))
      (node (ref "C16") (pin "2") (pinfunction "2_2") (pintype "passive"))
      (node (ref "IC2") (pin "5") (pinfunction "+IN_5") (pintype "input"))
      (node (ref "R11") (pin "2") (pinfunction "2_2") (pintype "passive"))
      (node (ref "SJ13") (pin "2") (pinfunction "2_2") (pintype "passive"))
    )
    (net (code "22") (name "Net-(IC2B--IN)") (class "Default")
      (node (ref "C28") (pin "1") (pinfunction "1_1") (pintype "passive"))
      (node (ref "IC2") (pin "6") (pinfunction "-IN_6") (pintype "input"))
      (node (ref "R24") (pin "1") (pinfunction "1_1") (pintype "passive"))
      (node (ref "R27") (pin "1") (pinfunction "1_1") (pintype "passive"))
    )
    (net (code "23") (name "Net-(IC2B-OUT)") (class "Default")
      (node (ref "C28") (pin "2") (pinfunction "2_2") (pintype "passive"))
      (node (ref "IC2") (pin "7") (pinfunction "OUT_7") (pintype "output"))
      (node (ref "R24") (pin "2") (pinfunction "2_2") (pintype "passive"))
      (node (ref "SJ13") (pin "1") (pinfunction "1_1") (pintype "passive"))
      (node (ref "U$1") (pin "4") (pinfunction "+IN_4") (pintype "passive"))
    )
    (net (code "24") (name "Net-(IC3A-+IN)") (class "Default")
      (node (ref "IC3") (pin "3") (pinfunction "+IN_3") (pintype "input"))
      (node (ref "R4") (pin "2") (pinfunction "2_2") (pintype "passive"))
      (node (ref "U$2") (pin "7") (pinfunction "OUT_7") (pintype "input"))
    )
    (net (code "25") (name "Net-(IC3A--IN)") (class "Default")
      (node (ref "C36") (pin "1") (pinfunction "1_1") (pintype "passive"))
      (node (ref "IC3") (pin "2") (pinfunction "-IN_2") (pintype "input"))
      (node (ref "R17") (pin "1") (pinfunction "1_1") (pintype "passive"))
      (node (ref "R19") (pin "2") (pinfunction "2_2") (pintype "passive"))
    )
    (net (code "26") (name "Net-(IC3A-OUT)") (class "Default")
      (node (ref "C36") (pin "2") (pinfunction "2_2") (pintype "passive"))
      (node (ref "C47") (pin "1") (pinfunction "1_1") (pintype "passive"))
      (node (ref "IC3") (pin "1") (pinfunction "OUT_1") (pintype "output"))
      (node (ref "R19") (pin "1") (pinfunction "1_1") (pintype "passive"))
    )
    (net (code "27") (name "Net-(IC3B-+IN)") (class "Default")
      (node (ref "C31") (pin "2") (pinfunction "2_2") (pintype "passive"))
      (node (ref "IC3") (pin "5") (pinfunction "+IN_5") (pintype "input"))
      (node (ref "R34") (pin "2") (pinfunction "S_2") (pintype "passive"))
      (node (ref "SJ11") (pin "2") (pinfunction "2_2") (pintype "passive"))
      (node (ref "SJ7") (pin "1") (pinfunction "1_1") (pintype "passive"))
    )
    (net (code "28") (name "Net-(IC3B--IN)") (class "Default")
      (node (ref "C34") (pin "1") (pinfunction "1_1") (pintype "passive"))
      (node (ref "IC3") (pin "6") (pinfunction "-IN_6") (pintype "input"))
      (node (ref "R7") (pin "1") (pinfunction "1_1") (pintype "passive"))
      (node (ref "R8") (pin "2") (pinfunction "2_2") (pintype "passive"))
    )
    (net (code "29") (name "Net-(IC3B-OUT)") (class "Default")
      (node (ref "C34") (pin "2") (pinfunction "2_2") (pintype "passive"))
      (node (ref "IC3") (pin "7") (pinfunction "OUT_7") (pintype "output"))
      (node (ref "R10") (pin "1") (pinfunction "1_1") (pintype "passive"))
      (node (ref "R8") (pin "1") (pinfunction "1_1") (pintype "passive"))
    )
    (net (code "30") (name "Net-(IC3C-+IN)") (class "Default")
      (node (ref "C12") (pin "2") (pinfunction "2_2") (pintype "passive"))
      (node (ref "IC3") (pin "10") (pinfunction "+IN_10") (pintype "input"))
      (node (ref "R35") (pin "2") (pinfunction "S_2") (pintype "passive"))
      (node (ref "SJ10") (pin "2") (pinfunction "2_2") (pintype "passive"))
      (node (ref "SJ8") (pin "1") (pinfunction "1_1") (pintype "passive"))
    )
    (net (code "31") (name "Net-(IC3C--IN)") (class "Default")
      (node (ref "C33") (pin "1") (pinfunction "1_1") (pintype "passive"))
      (node (ref "IC3") (pin "9") (pinfunction "-IN_9") (pintype "input"))
      (node (ref "R1") (pin "1") (pinfunction "1_1") (pintype "passive"))
      (node (ref "R2") (pin "2") (pinfunction "2_2") (pintype "passive"))
    )
    (net (code "32") (name "Net-(IC3C-OUT)") (class "Default")
      (node (ref "C33") (pin "2") (pinfunction "2_2") (pintype "passive"))
      (node (ref "IC3") (pin "8") (pinfunction "OUT_8") (pintype "output"))
      (node (ref "R2") (pin "1") (pinfunction "1_1") (pintype "passive"))
      (node (ref "R9") (pin "1") (pinfunction "1_1") (pintype "passive"))
    )
    (net (code "33") (name "Net-(IC3D-+IN)") (class "Default")
      (node (ref "IC3") (pin "12") (pinfunction "+IN_12") (pintype "input"))
      (node (ref "R3") (pin "2") (pinfunction "2_2") (pintype "passive"))
      (node (ref "U$1") (pin "7") (pinfunction "OUT_7") (pintype "input"))
    )
    (net (code "34") (name "Net-(IC3D--IN)") (class "Default")
      (node (ref "C35") (pin "1") (pinfunction "1_1") (pintype "passive"))
      (node (ref "IC3") (pin "13") (pinfunction "-IN_13") (pintype "input"))
      (node (ref "R15") (pin "1") (pinfunction "1_1") (pintype "passive"))
      (node (ref "R16") (pin "2") (pinfunction "2_2") (pintype "passive"))
    )
    (net (code "35") (name "Net-(IC3D-OUT)") (class "Default")
      (node (ref "C35") (pin "2") (pinfunction "2_2") (pintype "passive"))
      (node (ref "C46") (pin "1") (pinfunction "1_1") (pintype "passive"))
      (node (ref "IC3") (pin "14") (pinfunction "OUT_14") (pintype "output"))
      (node (ref "R16") (pin "1") (pinfunction "1_1") (pintype "passive"))
    )
    (net (code "36") (name "Net-(IC4A-+IN)") (class "Default")
      (node (ref "C19") (pin "1") (pinfunction "1_1") (pintype "passive"))
      (node (ref "C5") (pin "1") (pinfunction "1_1") (pintype "passive"))
      (node (ref "IC4") (pin "3") (pinfunction "+IN_3") (pintype "input"))
      (node (ref "R14") (pin "2") (pinfunction "2_2") (pintype "passive"))
      (node (ref "SJ14") (pin "2") (pinfunction "2_2") (pintype "passive"))
    )
    (net (code "37") (name "Net-(IC4A--IN)") (class "Default")
      (node (ref "C29") (pin "1") (pinfunction "1_1") (pintype "passive"))
      (node (ref "IC4") (pin "2") (pinfunction "-IN_2") (pintype "input"))
      (node (ref "R25") (pin "1") (pinfunction "1_1") (pintype "passive"))
      (node (ref "R28") (pin "2") (pinfunction "2_2") (pintype "passive"))
    )
    (net (code "38") (name "Net-(IC4A-OUT)") (class "Default")
      (node (ref "C29") (pin "2") (pinfunction "2_2") (pintype "passive"))
      (node (ref "IC4") (pin "1") (pinfunction "OUT_1") (pintype "output"))
      (node (ref "R25") (pin "2") (pinfunction "2_2") (pintype "passive"))
      (node (ref "SJ14") (pin "1") (pinfunction "1_1") (pintype "passive"))
      (node (ref "U$2") (pin "1") (pinfunction "-IN_1") (pintype "input"))
    )
    (net (code "39") (name "Net-(IC4B-+IN)") (class "Default")
      (node (ref "C18") (pin "2") (pinfunction "2_2") (pintype "passive"))
      (node (ref "C5") (pin "2") (pinfunction "2_2") (pintype "passive"))
      (node (ref "IC4") (pin "5") (pinfunction "+IN_5") (pintype "input"))
      (node (ref "R13") (pin "2") (pinfunction "2_2") (pintype "passive"))
      (node (ref "SJ15") (pin "2") (pinfunction "2_2") (pintype "passive"))
    )
    (net (code "40") (name "Net-(IC4B--IN)") (class "Default")
      (node (ref "C30") (pin "1") (pinfunction "1_1") (pintype "passive"))
      (node (ref "IC4") (pin "6") (pinfunction "-IN_6") (pintype "input"))
      (node (ref "R26") (pin "1") (pinfunction "1_1") (pintype "passive"))
      (node (ref "R28") (pin "1") (pinfunction "1_1") (pintype "passive"))
    )
    (net (code "41") (name "Net-(IC4B-OUT)") (class "Default")
      (node (ref "C30") (pin "2") (pinfunction "2_2") (pintype "passive"))
      (node (ref "IC4") (pin "7") (pinfunction "OUT_7") (pintype "output"))
      (node (ref "R26") (pin "2") (pinfunction "2_2") (pintype "passive"))
      (node (ref "SJ15") (pin "1") (pinfunction "1_1") (pintype "passive"))
      (node (ref "U$2") (pin "4") (pinfunction "+IN_4") (pintype "passive"))
    )
    (net (code "42") (name "Net-(IC5-CV)") (class "Default")
      (node (ref "C7") (pin "2") (pinfunction "2_2") (pintype "passive"))
      (node (ref "IC5") (pin "5") (pinfunction "CV_5") (pintype "input"))
    )
    (net (code "43") (name "Net-(IC5-DIS)") (class "Default")
      (node (ref "IC5") (pin "7") (pinfunction "DIS_7") (pintype "input"))
      (node (ref "R36") (pin "1") (pinfunction "1_1") (pintype "passive"))
      (node (ref "R37") (pin "2") (pinfunction "2_2") (pintype "passive"))
    )
    (net (code "44") (name "Net-(IC5-Q)") (class "Default")
      (node (ref "IC5") (pin "3") (pinfunction "Q_3") (pintype "output"))
      (node (ref "SJ9") (pin "1") (pinfunction "1_1") (pintype "passive"))
    )
    (net (code "45") (name "Net-(IC5-THR)") (class "Default")
      (node (ref "C13") (pin "1") (pinfunction "1_1") (pintype "passive"))
      (node (ref "C6") (pin "2") (pinfunction "2_2") (pintype "passive"))
      (node (ref "IC5") (pin "2") (pinfunction "TR_2") (pintype "input"))
      (node (ref "IC5") (pin "6") (pinfunction "THR_6") (pintype "input"))
      (node (ref "R37") (pin "1") (pinfunction "1_1") (pintype "passive"))
      (node (ref "SJ4") (pin "3") (pinfunction "3_3") (pintype "passive"))
    )
    (net (code "46") (name "Net-(IC6-BYP)") (class "Default")
      (node (ref "C38") (pin "2") (pinfunction "2_2") (pintype "passive"))
      (node (ref "IC6") (pin "4") (pinfunction "BYP_4") (pintype "passive"))
    )
    (net (code "47") (name "Net-(IC6-EN)") (class "Default")
      (node (ref "C37") (pin "2") (pinfunction "2_2") (pintype "passive"))
      (node (ref "D2") (pin "C") (pinfunction "C_C") (pintype "passive"))
      (node (ref "IC6") (pin "1") (pinfunction "IN_1") (pintype "input"))
      (node (ref "IC6") (pin "3") (pinfunction "EN_3") (pintype "input"))
    )
    (net (code "48") (name "Net-(IC6-OUT)") (class "Default")
      (node (ref "C39") (pin "2") (pinfunction "2_2") (pintype "passive"))
      (node (ref "IC6") (pin "5") (pinfunction "OUT_5") (pintype "output"))
      (node (ref "SJ1") (pin "3") (pinfunction "3_3") (pintype "passive"))
    )
    (net (code "49") (name "Net-(IC7-BYP)") (class "Default")
      (node (ref "C32") (pin "1") (pinfunction "1_1") (pintype "passive"))
      (node (ref "IC7") (pin "4") (pinfunction "BYP_4") (pintype "passive"))
    )
    (net (code "50") (name "Net-(IC7-EN)") (class "Default")
      (node (ref "C14") (pin "2") (pinfunction "2_2") (pintype "passive"))
      (node (ref "IC7") (pin "1") (pinfunction "IN_1") (pintype "input"))
      (node (ref "IC7") (pin "3") (pinfunction "EN_3") (pintype "input"))
      (node (ref "R38") (pin "2") (pinfunction "2_2") (pintype "passive"))
    )
    (net (code "51") (name "Net-(IC7-OUT)") (class "Default")
      (node (ref "C32") (pin "2") (pinfunction "2_2") (pintype "passive"))
      (node (ref "IC7") (pin "5") (pinfunction "OUT_5") (pintype "output"))
      (node (ref "SJ16") (pin "2") (pinfunction "2_2") (pintype "passive"))
    )
    (net (code "52") (name "Net-(IOL-Pad1)") (class "Default")
      (node (ref "IOL") (pin "1") (pinfunction "1_1") (pintype "passive"))
      (node (ref "TXD") (pin "1") (pinfunction "1_1") (pintype "passive"))
    )
    (net (code "53") (name "Net-(IOL-Pad2)") (class "Default")
      (node (ref "IOL") (pin "2") (pinfunction "2_2") (pintype "passive"))
      (node (ref "R20") (pin "2") (pinfunction "2_2") (pintype "passive"))
    )
    (net (code "54") (name "Net-(IOL-Pad3)") (class "Default")
      (node (ref "IOL") (pin "3") (pinfunction "3_3") (pintype "passive"))
      (node (ref "R33") (pin "2") (pinfunction "2_2") (pintype "passive"))
    )
    (net (code "55") (name "Net-(IOL-Pad4)") (class "Default")
      (node (ref "IOL") (pin "4") (pinfunction "4_4") (pintype "passive"))
      (node (ref "SJ9") (pin "3") (pinfunction "3_3") (pintype "passive"))
    )
    (net (code "56") (name "Net-(JP5-Pad1)") (class "Default")
      (node (ref "JP5") (pin "1") (pinfunction "1_1") (pintype "passive"))
      (node (ref "JP5") (pin "3") (pinfunction "3_3") (pintype "passive"))
      (node (ref "SJ6") (pin "1") (pinfunction "1_1") (pintype "passive"))
    )
    (net (code "57") (name "Net-(JP5-Pad2)") (class "Default")
      (node (ref "JP5") (pin "2") (pinfunction "2_2") (pintype "passive"))
      (node (ref "R11") (pin "1") (pinfunction "1_1") (pintype "passive"))
      (node (ref "SJ6") (pin "2") (pinfunction "2_2") (pintype "passive"))
    )
    (net (code "58") (name "Net-(JP5-Pad4)") (class "Default")
      (node (ref "JP5") (pin "4") (pinfunction "4_4") (pintype "passive"))
      (node (ref "R14") (pin "1") (pinfunction "1_1") (pintype "passive"))
    )
    (net (code "59") (name "Net-(JP5-Pad7)") (class "Default")
      (node (ref "JP5") (pin "7") (pinfunction "7_7") (pintype "passive"))
      (node (ref "R12") (pin "1") (pinfunction "1_1") (pintype "passive"))
    )
    (net (code "60") (name "Net-(JP5-Pad9)") (class "Default")
      (node (ref "JP5") (pin "9") (pinfunction "9_9") (pintype "passive"))
      (node (ref "R13") (pin "1") (pinfunction "1_1") (pintype "passive"))
      (node (ref "SJ17") (pin "1") (pinfunction "1_1") (pintype "passive"))
    )
    (net (code "61") (name "Net-(JP5-Pad10)") (class "Default")
      (node (ref "JP5") (pin "10") (pinfunction "10_10") (pintype "passive"))
      (node (ref "JP5") (pin "8") (pinfunction "8_8") (pintype "passive"))
      (node (ref "SJ17") (pin "2") (pinfunction "2_2") (pintype "passive"))
    )
    (net (code "62") (name "Net-(K1-A)") (class "Default")
      (node (ref "K1") (pin "1") (pinfunction "A_1") (pintype "passive"))
      (node (ref "K2") (pin "1") (pinfunction "A_1") (pintype "passive"))
      (node (ref "R33") (pin "1") (pinfunction "1_1") (pintype "passive"))
    )
    (net (code "63") (name "Net-(K1-DS1)") (class "Default")
      (node (ref "C44") (pin "2") (pinfunction "2_2") (pintype "passive"))
      (node (ref "K1") (pin "4") (pinfunction "DS1_4") (pintype "passive"))
      (node (ref "S2") (pin "1") (pinfunction "S_1") (pintype "passive"))
    )
    (net (code "64") (name "Net-(K2-DS1)") (class "Default")
      (node (ref "C13") (pin "2") (pinfunction "2_2") (pintype "passive"))
      (node (ref "K2") (pin "4") (pinfunction "DS1_4") (pintype "passive"))
      (node (ref "S2") (pin "4") (pinfunction "S_4") (pintype "passive"))
    )
    (net (code "65") (name "Net-(POWER-Pad5)") (class "Default")
      (node (ref "POWER") (pin "5") (pinfunction "5_5") (pintype "passive"))
      (node (ref "SJ1") (pin "1") (pinfunction "1_1") (pintype "passive"))
    )
    (net (code "66") (name "Net-(R20-Pad1)") (class "Default")
      (node (ref "R20") (pin "1") (pinfunction "1_1") (pintype "passive"))
      (node (ref "R22") (pin "2") (pinfunction "2_2") (pintype "passive"))
      (node (ref "RXD") (pin "1") (pinfunction "1_1") (pintype "passive"))
    )
    (net (code "67") (name "Net-(R30-Pad1)") (class "Default")
      (node (ref "R30") (pin "1") (pinfunction "1_1") (pintype "passive"))
      (node (ref "R40") (pin "2") (pinfunction "2_2") (pintype "passive"))
    )
    (net (code "68") (name "Net-(R30-Pad2)") (class "Default")
      (node (ref "R30") (pin "2") (pinfunction "2_2") (pintype "passive"))
      (node (ref "R32") (pin "2") (pinfunction "2_2") (pintype "passive"))
    )
    (net (code "69") (name "Net-(R31-Pad2)") (class "Default")
      (node (ref "R31") (pin "2") (pinfunction "2_2") (pintype "passive"))
      (node (ref "R41") (pin "1") (pinfunction "1_1") (pintype "passive"))
    )
    (net (code "70") (name "Net-(R34-A)") (class "Default")
      (node (ref "C25") (pin "2") (pinfunction "2_2") (pintype "passive"))
      (node (ref "R34") (pin "3") (pinfunction "A_3") (pintype "passive"))
      (node (ref "R35") (pin "3") (pinfunction "A_3") (pintype "passive"))
      (node (ref "R39") (pin "2") (pinfunction "2_2") (pintype "passive"))
    )
    (net (code "71") (name "Net-(R34-E)") (class "Default")
      (node (ref "R29") (pin "2") (pinfunction "2_2") (pintype "passive"))
      (node (ref "R34") (pin "1") (pinfunction "E_1") (pintype "passive"))
      (node (ref "R35") (pin "1") (pinfunction "E_1") (pintype "passive"))
      (node (ref "SJ10") (pin "1") (pinfunction "1_1") (pintype "passive"))
      (node (ref "SJ11") (pin "1") (pinfunction "1_1") (pintype "passive"))
    )
    (net (code "72") (name "Net-(SJ4-Pad1)") (class "Default")
      (node (ref "SJ4") (pin "1") (pinfunction "1_1") (pintype "passive"))
      (node (ref "SJ5") (pin "1") (pinfunction "1_1") (pintype "passive"))
      (node (ref "SJ9") (pin "2") (pinfunction "2_2") (pintype "passive"))
    )
    (net (code "73") (name "Net-(U$1-RG1)") (class "Default")
      (node (ref "R5") (pin "2") (pinfunction "2_2") (pintype "passive"))
      (node (ref "U$1") (pin "2") (pinfunction "RG1_2") (pintype "input"))
    )
    (net (code "74") (name "Net-(U$1-RG2)") (class "Default")
      (node (ref "R5") (pin "1") (pinfunction "1_1") (pintype "passive"))
      (node (ref "U$1") (pin "3") (pinfunction "RG2_3") (pintype "input"))
    )
    (net (code "75") (name "Net-(U$2-RG1)") (class "Default")
      (node (ref "R6") (pin "2") (pinfunction "2_2") (pintype "passive"))
      (node (ref "U$2") (pin "2") (pinfunction "RG1_2") (pintype "input"))
    )
    (net (code "76") (name "Net-(U$2-RG2)") (class "Default")
      (node (ref "R6") (pin "1") (pinfunction "1_1") (pintype "passive"))
      (node (ref "U$2") (pin "3") (pinfunction "RG2_3") (pintype "input"))
    )
    (net (code "77") (name "Net-(U$4-CLK)") (class "Default")
      (node (ref "SJ5") (pin "2") (pinfunction "2_2") (pintype "passive"))
      (node (ref "U$4") (pin "8") (pinfunction "CLK_8") (pintype "input"))
    )
    (net (code "78") (name "Net-(U$4-COM)") (class "Default")
      (node (ref "C2") (pin "2") (pinfunction "2_2") (pintype "passive"))
      (node (ref "U$4") (pin "1") (pinfunction "COM_1") (pintype "input"))
      (node (ref "U$4") (pin "6") (pinfunction "OS_6") (pintype "passive"))
    )
    (net (code "79") (name "Net-(U$4-IN)") (class "Default")
      (node (ref "D3") (pin "C") (pinfunction "C_C") (pintype "passive"))
      (node (ref "R9") (pin "2") (pinfunction "2_2") (pintype "passive"))
      (node (ref "U$4") (pin "2") (pinfunction "IN_2") (pintype "input"))
    )
    (net (code "80") (name "Net-(U$4-OUT)") (class "Default")
      (node (ref "R18") (pin "1") (pinfunction "1_1") (pintype "passive"))
      (node (ref "U$4") (pin "5") (pinfunction "OUT_5") (pintype "input"))
    )
    (net (code "81") (name "Net-(U$5-CLK)") (class "Default")
      (node (ref "SJ4") (pin "2") (pinfunction "2_2") (pintype "passive"))
      (node (ref "U$5") (pin "8") (pinfunction "CLK_8") (pintype "input"))
    )
    (net (code "82") (name "Net-(U$5-COM)") (class "Default")
      (node (ref "C3") (pin "2") (pinfunction "2_2") (pintype "passive"))
      (node (ref "U$5") (pin "1") (pinfunction "COM_1") (pintype "input"))
      (node (ref "U$5") (pin "6") (pinfunction "OS_6") (pintype "passive"))
    )
    (net (code "83") (name "Net-(U$5-IN)") (class "Default")
      (node (ref "D1") (pin "C") (pinfunction "C_C") (pintype "passive"))
      (node (ref "R10") (pin "2") (pinfunction "2_2") (pintype "passive"))
      (node (ref "U$5") (pin "2") (pinfunction "IN_2") (pintype "input"))
    )
    (net (code "84") (name "Net-(U$5-OUT)") (class "Default")
      (node (ref "R21") (pin "1") (pinfunction "1_1") (pintype "passive"))
      (node (ref "U$5") (pin "5") (pinfunction "OUT_5") (pintype "input"))
    )
    (net (code "85") (name "V+") (class "Default")
      (node (ref "C22") (pin "2") (pinfunction "2_2") (pintype "passive"))
      (node (ref "C23") (pin "2") (pinfunction "2_2") (pintype "passive"))
      (node (ref "C40") (pin "2") (pinfunction "2_2") (pintype "passive"))
      (node (ref "C42") (pin "1") (pinfunction "1_1") (pintype "passive"))
      (node (ref "C48") (pin "2") (pinfunction "2_2") (pintype "passive"))
      (node (ref "C51") (pin "1") (pinfunction "1_1") (pintype "passive"))
      (node (ref "C9") (pin "1") (pinfunction "1_1") (pintype "passive"))
      (node (ref "IC1") (pin "8") (pinfunction "V+_8") (pintype "power_in"))
      (node (ref "R38") (pin "1") (pinfunction "1_1") (pintype "passive"))
      (node (ref "U$1") (pin "8") (pinfunction "+V_8") (pintype "power_in"))
      (node (ref "U$2") (pin "8") (pinfunction "+V_8") (pintype "power_in"))
      (node (ref "U$7") (pin "6") (pinfunction "+VOUT_6") (pintype "passive"))
    )
    (net (code "86") (name "V-") (class "Default")
      (node (ref "C21") (pin "1") (pinfunction "1_1") (pintype "passive"))
      (node (ref "C27") (pin "1") (pinfunction "1_1") (pintype "passive"))
      (node (ref "C41") (pin "1") (pinfunction "1_1") (pintype "passive"))
      (node (ref "C43") (pin "1") (pinfunction "1_1") (pintype "passive"))
      (node (ref "C49") (pin "2") (pinfunction "2_2") (pintype "passive"))
      (node (ref "C50") (pin "1") (pinfunction "1_1") (pintype "passive"))
      (node (ref "C8") (pin "2") (pinfunction "2_2") (pintype "passive"))
      (node (ref "IC1") (pin "4") (pinfunction "V-_4") (pintype "power_in"))
      (node (ref "U$1") (pin "5") (pinfunction "-V_5") (pintype "power_in"))
      (node (ref "U$2") (pin "5") (pinfunction "-V_5") (pintype "power_in"))
      (node (ref "U$7") (pin "4") (pinfunction "-VOUT_4") (pintype "passive"))
    )
    (net (code "87") (name "VCC") (class "Default")
      (node (ref "C20") (pin "2") (pinfunction "2_2") (pintype "passive"))
      (node (ref "IC5") (pin "4") (pinfunction "R_4") (pintype "input"))
      (node (ref "IC5") (pin "8") (pinfunction "V+_8") (pintype "power_in"))
      (node (ref "R36") (pin "2") (pinfunction "2_2") (pintype "passive"))
      (node (ref "R41") (pin "2") (pinfunction "2_2") (pintype "passive"))
      (node (ref "SJ1") (pin "2") (pinfunction "2_2") (pintype "passive"))
      (node (ref "U$4") (pin "4") (pinfunction "+5V_4") (pintype "power_in"))
      (node (ref "U$4") (pin "7") (pinfunction "/SHDN_7") (pintype "input"))
      (node (ref "U$5") (pin "4") (pinfunction "+5V_4") (pintype "power_in"))
      (node (ref "U$5") (pin "7") (pinfunction "/SHDN_7") (pintype "input"))
      (node (ref "U$7") (pin "1") (pinfunction "+VIN_1") (pintype "passive"))
      (node (ref "VCC") (pin "1") (pinfunction "1_1") (pintype "passive"))
    )
    (net (code "88") (name "VEE") (class "Default")
      (node (ref "C26") (pin "2") (pinfunction "2_2") (pintype "passive"))
      (node (ref "IOH") (pin "8") (pinfunction "8_8") (pintype "passive"))
      (node (ref "R39") (pin "1") (pinfunction "1_1") (pintype "passive"))
      (node (ref "SJ16") (pin "1") (pinfunction "1_1") (pintype "passive"))
    )
    (net (code "89") (name "unconnected-(AD-Pad5)") (class "Default")
      (node (ref "AD") (pin "5") (pinfunction "5_5") (pintype "passive"))
    )
    (net (code "90") (name "unconnected-(AD-Pad6)") (class "Default")
      (node (ref "AD") (pin "6") (pinfunction "6_6") (pintype "passive"))
    )
    (net (code "91") (name "unconnected-(ICSP-Pad1)") (class "Default")
      (node (ref "ICSP") (pin "1") (pinfunction "1_1") (pintype "passive"))
    )
    (net (code "92") (name "unconnected-(ICSP-Pad2)") (class "Default")
      (node (ref "ICSP") (pin "2") (pinfunction "2_2") (pintype "passive"))
    )
    (net (code "93") (name "unconnected-(ICSP-Pad3)") (class "Default")
      (node (ref "ICSP") (pin "3") (pinfunction "3_3") (pintype "passive"))
    )
    (net (code "94") (name "unconnected-(ICSP-Pad4)") (class "Default")
      (node (ref "ICSP") (pin "4") (pinfunction "4_4") (pintype "passive"))
    )
    (net (code "95") (name "unconnected-(ICSP-Pad5)") (class "Default")
      (node (ref "ICSP") (pin "5") (pinfunction "5_5") (pintype "passive"))
    )
    (net (code "96") (name "unconnected-(ICSP-Pad6)") (class "Default")
      (node (ref "ICSP") (pin "6") (pinfunction "6_6") (pintype "passive"))
    )
    (net (code "97") (name "unconnected-(IOH-Pad1)") (class "Default")
      (node (ref "IOH") (pin "1") (pinfunction "1_1") (pintype "passive"))
    )
    (net (code "98") (name "unconnected-(IOH-Pad2)") (class "Default")
      (node (ref "IOH") (pin "2") (pinfunction "2_2") (pintype "passive"))
    )
    (net (code "99") (name "unconnected-(IOH-Pad3)") (class "Default")
      (node (ref "IOH") (pin "3") (pinfunction "3_3") (pintype "passive"))
    )
    (net (code "100") (name "unconnected-(IOH-Pad4)") (class "Default")
      (node (ref "IOH") (pin "4") (pinfunction "4_4") (pintype "passive"))
    )
    (net (code "101") (name "unconnected-(IOH-Pad5)") (class "Default")
      (node (ref "IOH") (pin "5") (pinfunction "5_5") (pintype "passive"))
    )
    (net (code "102") (name "unconnected-(IOH-Pad6)") (class "Default")
      (node (ref "IOH") (pin "6") (pinfunction "6_6") (pintype "passive"))
    )
    (net (code "103") (name "unconnected-(IOH-Pad7)") (class "Default")
      (node (ref "IOH") (pin "7") (pinfunction "7_7") (pintype "passive"))
    )
    (net (code "104") (name "unconnected-(IOH-Pad9)") (class "Default")
      (node (ref "IOH") (pin "9") (pinfunction "9_9") (pintype "passive"))
    )
    (net (code "105") (name "unconnected-(IOH-Pad10)") (class "Default")
      (node (ref "IOH") (pin "10") (pinfunction "10_10") (pintype "passive"))
    )
    (net (code "106") (name "unconnected-(IOL-Pad5)") (class "Default")
      (node (ref "IOL") (pin "5") (pinfunction "5_5") (pintype "passive"))
    )
    (net (code "107") (name "unconnected-(IOL-Pad6)") (class "Default")
      (node (ref "IOL") (pin "6") (pinfunction "6_6") (pintype "passive"))
    )
    (net (code "108") (name "unconnected-(IOL-Pad7)") (class "Default")
      (node (ref "IOL") (pin "7") (pinfunction "7_7") (pintype "passive"))
    )
    (net (code "109") (name "unconnected-(IOL-Pad8)") (class "Default")
      (node (ref "IOL") (pin "8") (pinfunction "8_8") (pintype "passive"))
    )
    (net (code "110") (name "unconnected-(POWER-Pad1)") (class "Default")
      (node (ref "POWER") (pin "1") (pinfunction "1_1") (pintype "passive"))
    )
    (net (code "111") (name "unconnected-(POWER-Pad2)") (class "Default")
      (node (ref "POWER") (pin "2") (pinfunction "2_2") (pintype "passive"))
    )
    (net (code "112") (name "unconnected-(POWER-Pad3)") (class "Default")
      (node (ref "POWER") (pin "3") (pinfunction "3_3") (pintype "passive"))
    )
    (net (code "113") (name "unconnected-(POWER-Pad4)") (class "Default")
      (node (ref "POWER") (pin "4") (pinfunction "4_4") (pintype "passive"))
    )
    (net (code "114") (name "unconnected-(R31-Pad1)") (class "Default")
      (node (ref "R31") (pin "1") (pinfunction "1_1") (pintype "passive"))
    )
    (net (code "115") (name "unconnected-(R32-Pad1)") (class "Default")
      (node (ref "R32") (pin "1") (pinfunction "1_1") (pintype "passive"))
    )
    (net (code "116") (name "unconnected-(R40-Pad1)") (class "Default")
      (node (ref "R40") (pin "1") (pinfunction "1_1") (pintype "passive"))
    )
    (net (code "117") (name "unconnected-(S2A-O-Pad3)") (class "Default")
      (node (ref "S2") (pin "3") (pinfunction "O_3") (pintype "passive"))
    )
    (net (code "118") (name "unconnected-(S2B-O-Pad6)") (class "Default")
      (node (ref "S2") (pin "6") (pinfunction "O_6") (pintype "passive"))
    )
  )
)
